# MFCC.net
KiCad netlist of a schematic drawn in EAGLE
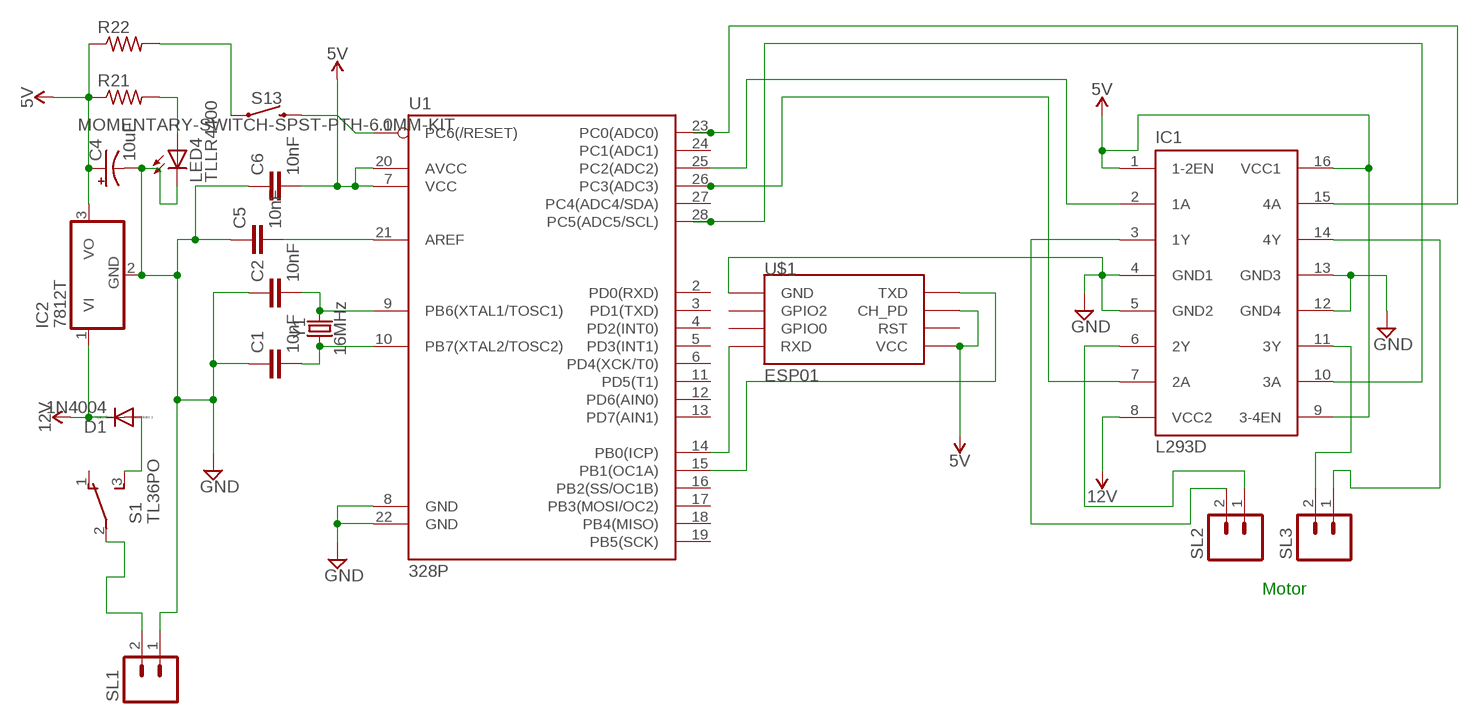
[diagram p0: schematic, sheet 1]

(export (version "E")
  (design (tool "Eeschema 10.0.6"))
  (components
    (comp (ref "C1")
      (value "10nF")
      (footprint "eagle-import:CAP-PTH-10MM")
      (libsource (lib "eagle-import") (part "10NF-PTH-10MM-10000V-1-%"))
    )
    (comp (ref "C2")
      (value "10nF")
      (footprint "eagle-import:CAP-PTH-10MM")
      (libsource (lib "eagle-import") (part "10NF-PTH-10MM-10000V-1-%"))
    )
    (comp (ref "C4")
      (value "10uF")
      (footprint "eagle-import:CPOL-RADIAL-2.5MM-5MM-KIT")
      (libsource (lib "eagle-import") (part "10UF-POLAR-RADIAL-2.5MM-KIT-25V-20%"))
    )
    (comp (ref "C5")
      (value "10nF")
      (footprint "eagle-import:CAP-PTH-10MM")
      (libsource (lib "eagle-import") (part "10NF-PTH-10MM-10000V-1-%"))
    )
    (comp (ref "C6")
      (value "10nF")
      (footprint "eagle-import:CAP-PTH-10MM")
      (libsource (lib "eagle-import") (part "10NF-PTH-10MM-10000V-1-%"))
    )
    (comp (ref "D1")
      (value "1N4004")
      (footprint "eagle-import:DO41-10")
      (libsource (lib "eagle-import") (part "1N4004"))
    )
    (comp (ref "IC1")
      (value "L293D")
      (footprint "eagle-import:DIL16")
      (libsource (lib "eagle-import") (part "L293D"))
    )
    (comp (ref "IC2")
      (value "7812T")
      (footprint "eagle-import:TO220H")
      (libsource (lib "eagle-import") (part "78T12"))
    )
    (comp (ref "LED4")
      (value "TLLR4400")
      (footprint "eagle-import:LED3MM")
      (fields (field (name "MF") "VISHAY SEMICONDUCTOR"))
      (libsource (lib "eagle-import") (part "TLLR4400"))
    )
    (comp (ref "R21")
      (value "R-US_0207/12")
      (footprint "eagle-import:0207_12")
      (libsource (lib "eagle-import") (part "R-US_0207/12"))
    )
    (comp (ref "R22")
      (value "R-US_0207/12")
      (footprint "eagle-import:0207_12")
      (libsource (lib "eagle-import") (part "R-US_0207/12"))
    )
    (comp (ref "S1")
      (value "TL36PO")
      (footprint "eagle-import:TL3XPO")
      (libsource (lib "eagle-import") (part "TL36PO"))
    )
    (comp (ref "S13")
      (value "MOMENTARY-SWITCH-SPST-PTH-6.0MM-KIT")
      (footprint "eagle-import:TACTILE_SWITCH_PTH_6.0MM_KIT")
      (libsource (lib "eagle-import") (part "MOMENTARY-SWITCH-SPST-PTH-6.0MM-KIT"))
    )
    (comp (ref "SL1")
      (value "MA02")
      (footprint "eagle-import:02PA")
      (libsource (lib "eagle-import") (part "MA02"))
    )
    (comp (ref "SL2")
      (value "MA02")
      (footprint "eagle-import:02PA")
      (libsource (lib "eagle-import") (part "MA02"))
    )
    (comp (ref "SL3")
      (value "MA02")
      (footprint "eagle-import:02PA")
      (libsource (lib "eagle-import") (part "MA02"))
    )
    (comp (ref "U$1")
      (value "ESP01")
      (footprint "eagle-import:ESP01")
      (libsource (lib "eagle-import") (part "ESP01"))
    )
    (comp (ref "U1")
      (value "328P")
      (footprint "eagle-import:DIP28")
      (libsource (lib "eagle-import") (part "ATMEGA328P_PDIP"))
    )
    (comp (ref "Y1")
      (value "16MHz")
      (footprint "eagle-import:HC49US")
      (libsource (lib "eagle-import") (part "CRYSTAL-16MHZPTH-HC49US"))
    )
  )
  (nets
    (net (code "1") (name "5V") (class "Default")
      (node (ref "C4") (pin "1") (pinfunction "+_1") (pintype "passive"))
      (node (ref "C6") (pin "2") (pinfunction "2_2") (pintype "passive"))
      (node (ref "IC1") (pin "1") (pinfunction "1-2EN_1") (pintype "input"))
      (node (ref "IC1") (pin "16") (pinfunction "VCC1_16") (pintype "power_in"))
      (node (ref "IC1") (pin "9") (pinfunction "3-4EN_9") (pintype "input"))
      (node (ref "IC2") (pin "3") (pinfunction "VO_3") (pintype "passive"))
      (node (ref "R21") (pin "1") (pinfunction "1_1") (pintype "passive"))
      (node (ref "R22") (pin "1") (pinfunction "1_1") (pintype "passive"))
      (node (ref "U$1") (pin "CH_PD") (pinfunction "CH_PD_CH_PD") (pintype "bidirectional"))
      (node (ref "U$1") (pin "VCC") (pinfunction "VCC_VCC") (pintype "bidirectional"))
      (node (ref "U1") (pin "20") (pinfunction "AVCC_20") (pintype "bidirectional"))
      (node (ref "U1") (pin "7") (pinfunction "VCC_7") (pintype "bidirectional"))
    )
    (net (code "2") (name "12V") (class "Default")
      (node (ref "D1") (pin "C") (pinfunction "C_C") (pintype "passive"))
      (node (ref "IC1") (pin "8") (pinfunction "VCC2_8") (pintype "power_in"))
      (node (ref "IC2") (pin "1") (pinfunction "VI_1") (pintype "input"))
    )
    (net (code "3") (name "GND") (class "Default")
      (node (ref "C1") (pin "1") (pinfunction "1_1") (pintype "passive"))
      (node (ref "C2") (pin "1") (pinfunction "1_1") (pintype "passive"))
      (node (ref "C4") (pin "2") (pinfunction "-_2") (pintype "passive"))
      (node (ref "C5") (pin "1") (pinfunction "1_1") (pintype "passive"))
      (node (ref "C6") (pin "1") (pinfunction "1_1") (pintype "passive"))
      (node (ref "IC1") (pin "12") (pinfunction "GND4_12") (pintype "power_in"))
      (node (ref "IC1") (pin "13") (pinfunction "GND3_13") (pintype "power_in"))
      (node (ref "IC1") (pin "4") (pinfunction "GND1_4") (pintype "power_in"))
      (node (ref "IC1") (pin "5") (pinfunction "GND2_5") (pintype "power_in"))
      (node (ref "IC2") (pin "2") (pinfunction "GND_2") (pintype "passive"))
      (node (ref "LED4") (pin "K") (pinfunction "C_K") (pintype "passive"))
      (node (ref "SL1") (pin "1") (pinfunction "1_1") (pintype "passive"))
      (node (ref "U$1") (pin "GND") (pinfunction "GND_GND") (pintype "bidirectional"))
      (node (ref "U1") (pin "22") (pinfunction "GND_22") (pintype "bidirectional"))
      (node (ref "U1") (pin "8") (pinfunction "GND_8") (pintype "bidirectional"))
    )
    (net (code "4") (name "Net-(IC1-1A)") (class "Default")
      (node (ref "IC1") (pin "2") (pinfunction "1A_2") (pintype "input"))
      (node (ref "U1") (pin "25") (pinfunction "PC2(ADC2)_25") (pintype "bidirectional"))
    )
    (net (code "5") (name "Net-(IC1-1Y)") (class "Default")
      (node (ref "IC1") (pin "3") (pinfunction "1Y_3") (pintype "output"))
      (node (ref "SL2") (pin "2") (pinfunction "2_2") (pintype "passive"))
    )
    (net (code "6") (name "Net-(IC1-2A)") (class "Default")
      (node (ref "IC1") (pin "7") (pinfunction "2A_7") (pintype "input"))
      (node (ref "U1") (pin "26") (pinfunction "PC3(ADC3)_26") (pintype "bidirectional"))
    )
    (net (code "7") (name "Net-(IC1-2Y)") (class "Default")
      (node (ref "IC1") (pin "6") (pinfunction "2Y_6") (pintype "output"))
      (node (ref "SL2") (pin "1") (pinfunction "1_1") (pintype "passive"))
    )
    (net (code "8") (name "Net-(IC1-3A)") (class "Default")
      (node (ref "IC1") (pin "10") (pinfunction "3A_10") (pintype "input"))
      (node (ref "U1") (pin "28") (pinfunction "PC5(ADC5/SCL)_28") (pintype "bidirectional"))
    )
    (net (code "9") (name "Net-(IC1-3Y)") (class "Default")
      (node (ref "IC1") (pin "11") (pinfunction "3Y_11") (pintype "output"))
      (node (ref "SL3") (pin "2") (pinfunction "2_2") (pintype "passive"))
    )
    (net (code "10") (name "Net-(IC1-4A)") (class "Default")
      (node (ref "IC1") (pin "15") (pinfunction "4A_15") (pintype "input"))
      (node (ref "U1") (pin "23") (pinfunction "PC0(ADC0)_23") (pintype "bidirectional"))
    )
    (net (code "11") (name "Net-(IC1-4Y)") (class "Default")
      (node (ref "IC1") (pin "14") (pinfunction "4Y_14") (pintype "output"))
      (node (ref "SL3") (pin "1") (pinfunction "1_1") (pintype "passive"))
    )
    (net (code "12") (name "Net-(LED4-PadA)") (class "Default")
      (node (ref "LED4") (pin "A") (pinfunction "A_A") (pintype "passive"))
      (node (ref "R21") (pin "2") (pinfunction "2_2") (pintype "passive"))
    )
    (net (code "13") (name "Net-(R22-Pad2)") (class "Default")
      (node (ref "R22") (pin "2") (pinfunction "2_2") (pintype "passive"))
      (node (ref "S13") (pin "1") (pinfunction "1_1") (pintype "passive"))
    )
    (net (code "14") (name "Net-(S1-P)") (class "Default")
      (node (ref "S1") (pin "2") (pinfunction "P_2") (pintype "passive"))
      (node (ref "SL1") (pin "2") (pinfunction "2_2") (pintype "passive"))
    )
    (net (code "15") (name "Net-(S1-S)") (class "Default")
      (node (ref "D1") (pin "A") (pinfunction "A_A") (pintype "passive"))
      (node (ref "S1") (pin "3") (pinfunction "S_3") (pintype "passive"))
    )
    (net (code "16") (name "Net-(S13-2)") (class "Default")
      (node (ref "S13") (pin "3") (pinfunction "2_3") (pintype "passive"))
      (node (ref "U1") (pin "1") (pinfunction "PC6(/RESET)_1") (pintype "bidirectional"))
    )
    (net (code "17") (name "Net-(U$1-RXD)") (class "Default")
      (node (ref "U$1") (pin "RX") (pinfunction "RXD_RX") (pintype "bidirectional"))
      (node (ref "U1") (pin "14") (pinfunction "PB0(ICP)_14") (pintype "bidirectional"))
    )
    (net (code "18") (name "Net-(U$1-TXD)") (class "Default")
      (node (ref "U$1") (pin "TX") (pinfunction "TXD_TX") (pintype "bidirectional"))
      (node (ref "U1") (pin "15") (pinfunction "PB1(OC1A)_15") (pintype "bidirectional"))
    )
    (net (code "19") (name "Net-(U1-AREF)") (class "Default")
      (node (ref "C5") (pin "2") (pinfunction "2_2") (pintype "passive"))
      (node (ref "U1") (pin "21") (pinfunction "AREF_21") (pintype "bidirectional"))
    )
    (net (code "20") (name "Net-(U1-PB6(XTAL1{slash}TOSC1))") (class "Default")
      (node (ref "C2") (pin "2") (pinfunction "2_2") (pintype "passive"))
      (node (ref "U1") (pin "9") (pinfunction "PB6(XTAL1/TOSC1)_9") (pintype "bidirectional"))
      (node (ref "Y1") (pin "2") (pinfunction "2_2") (pintype "passive"))
    )
    (net (code "21") (name "Net-(U1-PB7(XTAL2{slash}TOSC2))") (class "Default")
      (node (ref "C1") (pin "2") (pinfunction "2_2") (pintype "passive"))
      (node (ref "U1") (pin "10") (pinfunction "PB7(XTAL2/TOSC2)_10") (pintype "bidirectional"))
      (node (ref "Y1") (pin "1") (pinfunction "1_1") (pintype "passive"))
    )
    (net (code "22") (name "unconnected-(S1-O-Pad1)") (class "Default")
      (node (ref "S1") (pin "1") (pinfunction "O_1") (pintype "passive"))
    )
    (net (code "23") (name "unconnected-(U$1-PadGPIO0)") (class "Default")
      (node (ref "U$1") (pin "GPIO0") (pinfunction "GPIO0_GPIO0") (pintype "bidirectional"))
    )
    (net (code "24") (name "unconnected-(U$1-PadGPIO2)") (class "Default")
      (node (ref "U$1") (pin "GPIO2") (pinfunction "GPIO2_GPIO2") (pintype "bidirectional"))
    )
    (net (code "25") (name "unconnected-(U$1-PadRST)") (class "Default")
      (node (ref "U$1") (pin "RST") (pinfunction "RST_RST") (pintype "bidirectional"))
    )
    (net (code "26") (name "unconnected-(U1-PB2(SS{slash}OC1B)-Pad16)") (class "Default")
      (node (ref "U1") (pin "16") (pinfunction "PB2(SS/OC1B)_16") (pintype "bidirectional"))
    )
    (net (code "27") (name "unconnected-(U1-PB3(MOSI{slash}OC2)-Pad17)") (class "Default")
      (node (ref "U1") (pin "17") (pinfunction "PB3(MOSI/OC2)_17") (pintype "bidirectional"))
    )
    (net (code "28") (name "unconnected-(U1-PB4(MISO)-Pad18)") (class "Default")
      (node (ref "U1") (pin "18") (pinfunction "PB4(MISO)_18") (pintype "bidirectional"))
    )
    (net (code "29") (name "unconnected-(U1-PB5(SCK)-Pad19)") (class "Default")
      (node (ref "U1") (pin "19") (pinfunction "PB5(SCK)_19") (pintype "bidirectional"))
    )
    (net (code "30") (name "unconnected-(U1-PC1(ADC1)-Pad24)") (class "Default")
      (node (ref "U1") (pin "24") (pinfunction "PC1(ADC1)_24") (pintype "bidirectional"))
    )
    (net (code "31") (name "unconnected-(U1-PC4(ADC4{slash}SDA)-Pad27)") (class "Default")
      (node (ref "U1") (pin "27") (pinfunction "PC4(ADC4/SDA)_27") (pintype "bidirectional"))
    )
    (net (code "32") (name "unconnected-(U1-PD0(RXD)-Pad2)") (class "Default")
      (node (ref "U1") (pin "2") (pinfunction "PD0(RXD)_2") (pintype "bidirectional"))
    )
    (net (code "33") (name "unconnected-(U1-PD1(TXD)-Pad3)") (class "Default")
      (node (ref "U1") (pin "3") (pinfunction "PD1(TXD)_3") (pintype "bidirectional"))
    )
    (net (code "34") (name "unconnected-(U1-PD2(INT0)-Pad4)") (class "Default")
      (node (ref "U1") (pin "4") (pinfunction "PD2(INT0)_4") (pintype "bidirectional"))
    )
    (net (code "35") (name "unconnected-(U1-PD3(INT1)-Pad5)") (class "Default")
      (node (ref "U1") (pin "5") (pinfunction "PD3(INT1)_5") (pintype "bidirectional"))
    )
    (net (code "36") (name "unconnected-(U1-PD4(XCK{slash}T0)-Pad6)") (class "Default")
      (node (ref "U1") (pin "6") (pinfunction "PD4(XCK/T0)_6") (pintype "bidirectional"))
    )
    (net (code "37") (name "unconnected-(U1-PD5(T1)-Pad11)") (class "Default")
      (node (ref "U1") (pin "11") (pinfunction "PD5(T1)_11") (pintype "bidirectional"))
    )
    (net (code "38") (name "unconnected-(U1-PD6(AIN0)-Pad12)") (class "Default")
      (node (ref "U1") (pin "12") (pinfunction "PD6(AIN0)_12") (pintype "bidirectional"))
    )
    (net (code "39") (name "unconnected-(U1-PD7(AIN1)-Pad13)") (class "Default")
      (node (ref "U1") (pin "13") (pinfunction "PD7(AIN1)_13") (pintype "bidirectional"))
    )
  )
)
